# COM_GSM.net
KiCad netlist of a schematic drawn in Altium Designer
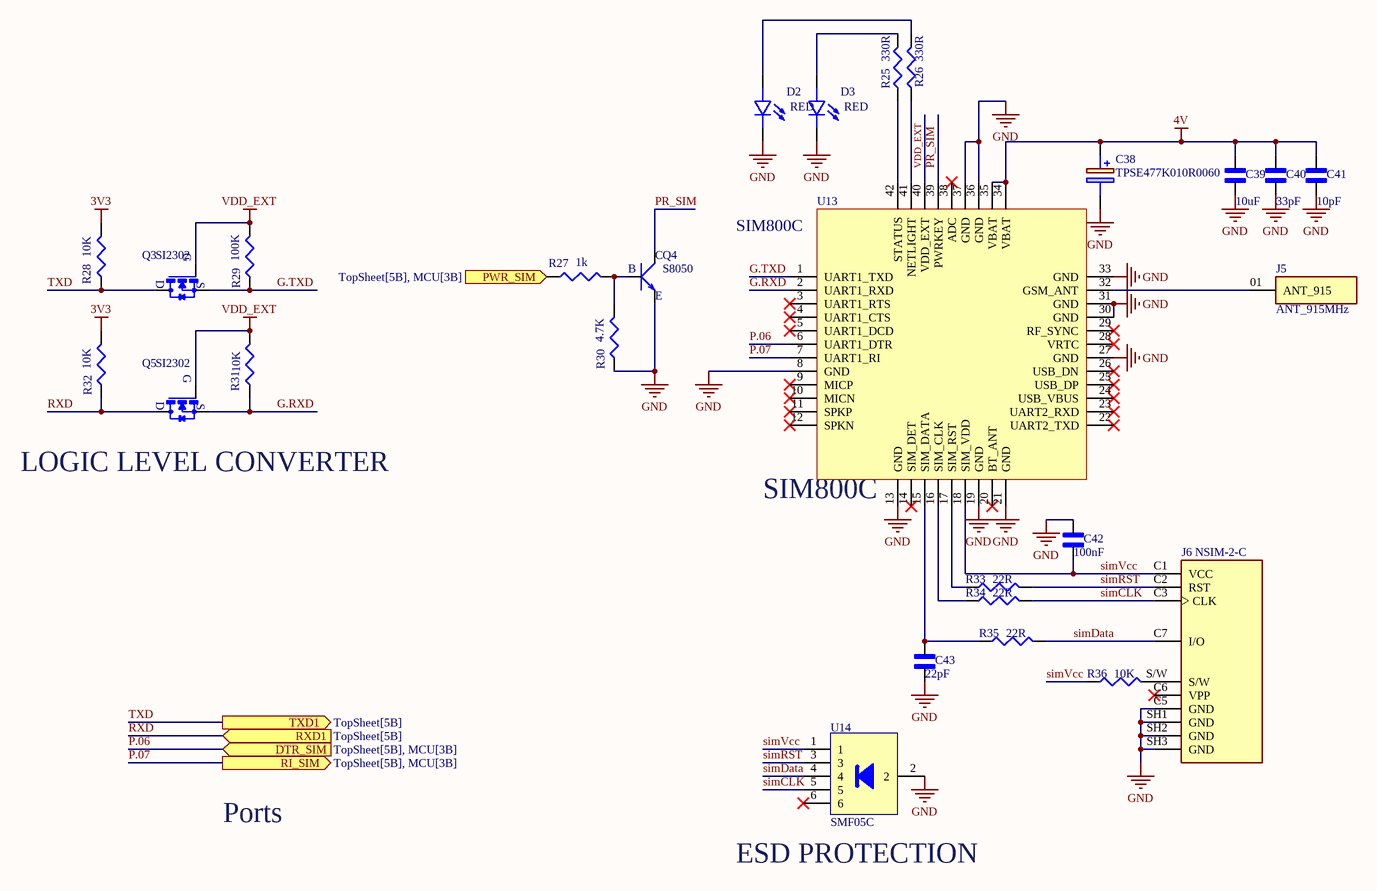
[diagram p0: COM_GSM.SchDoc]

(export (version "E")
  (design (tool "Eeschema 10.0.6"))
  (components
    (comp (ref "C38")
      (value "TPSE477K010R0060")
      (footprint "CAPPM7344X430N")
      (fields (field (name "MOUSER PART NUMBER") "581-TPSE477K010R0060"))
      (libsource (lib "TPSE477K010R0060") (part "TPSE477K010R0060"))
    )
    (comp (ref "C39")
      (value "10uF")
      (footprint "C0603")
      (fields (field (name "MF") "Murata") (field (name "MP") "GJM1555C1HR10BB01J"))
      (libsource (lib "common component") (part "Capacitor non polar"))
    )
    (comp (ref "C40")
      (value "33pF")
      (footprint "C0603")
      (fields (field (name "MF") "Murata") (field (name "MP") "GJM1555C1HR10BB01J"))
      (libsource (lib "common component") (part "Capacitor non polar"))
    )
    (comp (ref "C41")
      (value "10pF")
      (footprint "C0603")
      (fields (field (name "MF") "Murata") (field (name "MP") "GJM1555C1HR10BB01J"))
      (libsource (lib "common component") (part "Capacitor non polar"))
    )
    (comp (ref "C42")
      (value "100nF")
      (footprint "C0402")
      (fields (field (name "MF") "Murata") (field (name "MP") "GJM1555C1HR10BB01J"))
      (libsource (lib "common component") (part "Capacitor non polar"))
    )
    (comp (ref "C43")
      (value "22pF")
      (footprint "C0402")
      (fields (field (name "MF") "Murata") (field (name "MP") "GJM1555C1HR10BB01J"))
      (libsource (lib "common component") (part "Capacitor non polar"))
    )
    (comp (ref "D2")
      (value "RED")
      (footprint "0603D-B")
      (description "Generic LED SMD")
      (fields (field (name "MF") "Osram") (field (name "MP") "LHN974 RED LED 1206"))
      (libsource (lib "common component") (part "LED"))
    )
    (comp (ref "D3")
      (value "RED")
      (footprint "0603D-B")
      (description "Generic LED SMD")
      (fields (field (name "MF") "Osram") (field (name "MP") "LHN974 RED LED 1206"))
      (libsource (lib "common component") (part "LED"))
    )
    (comp (ref "J5")
      (value "ANT_915MHz")
      (footprint "SAMTEC_HTSW-101-24-LM-S")
      (fields (field (name "MP") "HTSW-101-24-LM-S"))
      (libsource (lib "ANT 915MHz") (part "ANT_915MHz"))
    )
    (comp (ref "J6")
      (value "NSIM-2-C")
      (footprint "CUI_NSIM-2-C")
      (fields (field (name "MF") "Same Sky"))
      (libsource (lib "NSIM-2-C") (part "NSIM-2-C"))
    )
    (comp (ref "Q3")
      (value "SI2302")
      (footprint "SOT23")
      (description "N-Channel 20 V 2.6A (Ta) 710mW (Ta) Surface Mount SOT-23-3 (TO-236)")
      (fields (field (name "MF") "Vishay Siliconix"))
      (libsource (lib "SI2302") (part "SI2302"))
    )
    (comp (ref "Q4")
      (value "S8050")
      (footprint "SOT95P237X112-3N")
      (description "Bipolar (BJT) Transistor NPN 25 V 500 mA 150MHz 300 mW Surface Mount SOT-23")
      (fields (field (name "MF") "UMW"))
      (libsource (lib "S8050") (part "S8050"))
    )
    (comp (ref "Q5")
      (value "SI2302")
      (footprint "SOT23")
      (description "N-Channel 20 V 2.6A (Ta) 710mW (Ta) Surface Mount SOT-23-3 (TO-236)")
      (fields (field (name "MF") "Vishay Siliconix"))
      (libsource (lib "SI2302") (part "SI2302"))
    )
    (comp (ref "R25")
      (value "330R")
      (footprint "R0603")
      (libsource (lib "common component") (part "Resistor"))
    )
    (comp (ref "R26")
      (value "330R")
      (footprint "R0603")
      (libsource (lib "common component") (part "Resistor"))
    )
    (comp (ref "R27") (value "1k") (footprint "R0603") (libsource (lib "common component") (part "Resistor")))
    (comp (ref "R28")
      (value "10K")
      (footprint "R0603")
      (libsource (lib "common component") (part "Resistor"))
    )
    (comp (ref "R29")
      (value "100K")
      (footprint "R0603")
      (libsource (lib "common component") (part "Resistor"))
    )
    (comp (ref "R30")
      (value "4.7K")
      (footprint "R0603")
      (libsource (lib "common component") (part "Resistor"))
    )
    (comp (ref "R31")
      (value "10K")
      (footprint "R0603")
      (libsource (lib "common component") (part "Resistor"))
    )
    (comp (ref "R32")
      (value "10K")
      (footprint "R0603")
      (libsource (lib "common component") (part "Resistor"))
    )
    (comp (ref "R33")
      (value "22R")
      (footprint "R0402")
      (libsource (lib "common component") (part "Resistor"))
    )
    (comp (ref "R34")
      (value "22R")
      (footprint "R0402")
      (libsource (lib "common component") (part "Resistor"))
    )
    (comp (ref "R35")
      (value "22R")
      (footprint "R0402")
      (libsource (lib "common component") (part "Resistor"))
    )
    (comp (ref "R36")
      (value "10K")
      (footprint "R0402")
      (libsource (lib "common component") (part "Resistor"))
    )
    (comp (ref "U13")
      (value "SIM800C GSM/GPRS Module")
      (footprint "SMD")
      (fields (field (name "DEVICENAME") "SIM800C"))
      (libsource (lib "SIM800C") (part "GSM_SIM800C"))
    )
    (comp (ref "U14") (value "SOT363") (footprint "SOT363") (libsource (lib "SMF05C") (part "SMF05C")))
  )
  (nets
    (net (code "1") (name "/G.RXD") (class "Default")
      (node (ref "Q5") (pin "2") (pinfunction "S_2") (pintype "passive"))
      (node (ref "R31") (pin "1") (pinfunction "1_1") (pintype "passive"))
      (node (ref "U13") (pin "2") (pinfunction "UART1_RXD_2") (pintype "passive"))
    )
    (net (code "2") (name "/G.TXD") (class "Default")
      (node (ref "Q3") (pin "2") (pinfunction "S_2") (pintype "passive"))
      (node (ref "R29") (pin "1") (pinfunction "1_1") (pintype "passive"))
      (node (ref "U13") (pin "1") (pinfunction "UART1_TXD_1") (pintype "passive"))
    )
    (net (code "3") (name "/P.06") (class "Default")
      (node (ref "U13") (pin "6") (pinfunction "UART1_DTR_6") (pintype "passive"))
    )
    (net (code "4") (name "/P.07") (class "Default")
      (node (ref "U13") (pin "7") (pinfunction "UART1_RI_7") (pintype "passive"))
    )
    (net (code "5") (name "/PR_SIM") (class "Default")
      (node (ref "Q4") (pin "3") (pinfunction "C_3") (pintype "passive"))
      (node (ref "U13") (pin "39") (pinfunction "PWRKEY_39") (pintype "passive"))
    )
    (net (code "6") (name "/PWR_SIM") (class "Default")
      (node (ref "R27") (pin "1") (pinfunction "1_1") (pintype "passive"))
    )
    (net (code "7") (name "/RXD") (class "Default")
      (node (ref "Q5") (pin "3") (pinfunction "D_3") (pintype "passive"))
      (node (ref "R32") (pin "1") (pinfunction "1_1") (pintype "passive"))
    )
    (net (code "8") (name "/TXD") (class "Default")
      (node (ref "Q3") (pin "3") (pinfunction "D_3") (pintype "passive"))
      (node (ref "R28") (pin "1") (pinfunction "1_1") (pintype "passive"))
    )
    (net (code "9") (name "/simCLK") (class "Default")
      (node (ref "J6") (pin "C3") (pinfunction "CLK_C3") (pintype "passive"))
      (node (ref "R34") (pin "2") (pinfunction "2_2") (pintype "passive"))
      (node (ref "U14") (pin "5") (pinfunction "5_5") (pintype "passive"))
    )
    (net (code "10") (name "/simData") (class "Default")
      (node (ref "J6") (pin "C7") (pinfunction "I/O_C7") (pintype "passive"))
      (node (ref "R35") (pin "2") (pinfunction "2_2") (pintype "passive"))
      (node (ref "U14") (pin "4") (pinfunction "4_4") (pintype "passive"))
    )
    (net (code "11") (name "/simRST") (class "Default")
      (node (ref "J6") (pin "C2") (pinfunction "RST_C2") (pintype "passive"))
      (node (ref "R33") (pin "2") (pinfunction "2_2") (pintype "passive"))
      (node (ref "U14") (pin "3") (pinfunction "3_3") (pintype "passive"))
    )
    (net (code "12") (name "/simVcc") (class "Default")
      (node (ref "C42") (pin "1") (pinfunction "1_1") (pintype "passive"))
      (node (ref "J6") (pin "C1") (pinfunction "VCC_C1") (pintype "passive"))
      (node (ref "R36") (pin "1") (pinfunction "1_1") (pintype "passive"))
      (node (ref "U13") (pin "18") (pinfunction "SIM_VDD_18") (pintype "passive"))
      (node (ref "U14") (pin "1") (pinfunction "1_1") (pintype "passive"))
    )
    (net (code "13") (name "3V3") (class "Default")
      (node (ref "R28") (pin "2") (pinfunction "2_2") (pintype "passive"))
      (node (ref "R32") (pin "2") (pinfunction "2_2") (pintype "passive"))
    )
    (net (code "14") (name "4V") (class "Default")
      (node (ref "C38") (pin "1") (pinfunction "+_1") (pintype "passive"))
      (node (ref "C39") (pin "2") (pinfunction "2_2") (pintype "passive"))
      (node (ref "C40") (pin "2") (pinfunction "2_2") (pintype "passive"))
      (node (ref "C41") (pin "2") (pinfunction "2_2") (pintype "passive"))
      (node (ref "U13") (pin "34") (pinfunction "VBAT_34") (pintype "passive"))
      (node (ref "U13") (pin "35") (pinfunction "VBAT_35") (pintype "passive"))
    )
    (net (code "15") (name "GND") (class "Default")
      (node (ref "C38") (pin "2") (pinfunction "-_2") (pintype "passive"))
      (node (ref "C39") (pin "1") (pinfunction "1_1") (pintype "passive"))
      (node (ref "C40") (pin "1") (pinfunction "1_1") (pintype "passive"))
      (node (ref "C41") (pin "1") (pinfunction "1_1") (pintype "passive"))
      (node (ref "C42") (pin "2") (pinfunction "2_2") (pintype "passive"))
      (node (ref "C43") (pin "1") (pinfunction "1_1") (pintype "passive"))
      (node (ref "D2") (pin "2") (pinfunction "NEG_2") (pintype "passive"))
      (node (ref "D3") (pin "2") (pinfunction "NEG_2") (pintype "passive"))
      (node (ref "J6") (pin "C5") (pinfunction "GND_C5") (pintype "passive"))
      (node (ref "J6") (pin "SH1") (pinfunction "GND_SH1") (pintype "passive"))
      (node (ref "J6") (pin "SH2") (pinfunction "GND_SH2") (pintype "passive"))
      (node (ref "J6") (pin "SH3") (pinfunction "GND_SH3") (pintype "passive"))
      (node (ref "Q4") (pin "2") (pinfunction "E_2") (pintype "passive"))
      (node (ref "R30") (pin "1") (pinfunction "1_1") (pintype "passive"))
      (node (ref "U13") (pin "13") (pinfunction "GND_13") (pintype "passive"))
      (node (ref "U13") (pin "19") (pinfunction "GND_19") (pintype "passive"))
      (node (ref "U13") (pin "21") (pinfunction "GND_21") (pintype "passive"))
      (node (ref "U13") (pin "27") (pinfunction "GND_27") (pintype "passive"))
      (node (ref "U13") (pin "30") (pinfunction "GND_30") (pintype "passive"))
      (node (ref "U13") (pin "31") (pinfunction "GND_31") (pintype "passive"))
      (node (ref "U13") (pin "33") (pinfunction "GND_33") (pintype "passive"))
      (node (ref "U13") (pin "36") (pinfunction "GND_36") (pintype "passive"))
      (node (ref "U13") (pin "37") (pinfunction "GND_37") (pintype "passive"))
      (node (ref "U13") (pin "8") (pinfunction "GND_8") (pintype "passive"))
      (node (ref "U14") (pin "2") (pinfunction "2_2") (pintype "passive"))
    )
    (net (code "16") (name "Net-(D2-POS)") (class "Default")
      (node (ref "D2") (pin "1") (pinfunction "POS_1") (pintype "passive"))
      (node (ref "R26") (pin "2") (pinfunction "2_2") (pintype "passive"))
    )
    (net (code "17") (name "Net-(D3-POS)") (class "Default")
      (node (ref "D3") (pin "1") (pinfunction "POS_1") (pintype "passive"))
      (node (ref "R25") (pin "2") (pinfunction "2_2") (pintype "passive"))
    )
    (net (code "18") (name "Net-(J5-ANT_915)") (class "Default")
      (node (ref "J5") (pin "01") (pinfunction "ANT_915_01") (pintype "passive"))
      (node (ref "U13") (pin "32") (pinfunction "GSM_ANT_32") (pintype "passive"))
    )
    (net (code "19") (name "Net-(J6-PadS{slash}W)") (class "Default")
      (node (ref "J6") (pin "S/W") (pinfunction "S/W_S/W") (pintype "passive"))
      (node (ref "R36") (pin "2") (pinfunction "2_2") (pintype "passive"))
    )
    (net (code "20") (name "Net-(Q4-B)") (class "Default")
      (node (ref "Q4") (pin "1") (pinfunction "B_1") (pintype "passive"))
      (node (ref "R27") (pin "2") (pinfunction "2_2") (pintype "passive"))
      (node (ref "R30") (pin "2") (pinfunction "2_2") (pintype "passive"))
    )
    (net (code "21") (name "Net-(U13-NETLIGHT)") (class "Default")
      (node (ref "R26") (pin "1") (pinfunction "1_1") (pintype "passive"))
      (node (ref "U13") (pin "41") (pinfunction "NETLIGHT_41") (pintype "passive"))
    )
    (net (code "22") (name "Net-(U13-SIM_CLK)") (class "Default")
      (node (ref "R34") (pin "1") (pinfunction "1_1") (pintype "passive"))
      (node (ref "U13") (pin "16") (pinfunction "SIM_CLK_16") (pintype "passive"))
    )
    (net (code "23") (name "Net-(U13-SIM_DATA)") (class "Default")
      (node (ref "C43") (pin "2") (pinfunction "2_2") (pintype "passive"))
      (node (ref "R35") (pin "1") (pinfunction "1_1") (pintype "passive"))
      (node (ref "U13") (pin "15") (pinfunction "SIM_DATA_15") (pintype "passive"))
    )
    (net (code "24") (name "Net-(U13-SIM_RST)") (class "Default")
      (node (ref "R33") (pin "1") (pinfunction "1_1") (pintype "passive"))
      (node (ref "U13") (pin "17") (pinfunction "SIM_RST_17") (pintype "passive"))
    )
    (net (code "25") (name "Net-(U13-STATUS)") (class "Default")
      (node (ref "R25") (pin "1") (pinfunction "1_1") (pintype "passive"))
      (node (ref "U13") (pin "42") (pinfunction "STATUS_42") (pintype "passive"))
    )
    (net (code "26") (name "VDD_EXT") (class "Default")
      (node (ref "Q3") (pin "1") (pinfunction "G_1") (pintype "passive"))
      (node (ref "Q5") (pin "1") (pinfunction "G_1") (pintype "passive"))
      (node (ref "R29") (pin "2") (pinfunction "2_2") (pintype "passive"))
      (node (ref "R31") (pin "2") (pinfunction "2_2") (pintype "passive"))
      (node (ref "U13") (pin "40") (pinfunction "VDD_EXT_40") (pintype "passive"))
    )
    (net (code "27") (name "unconnected-(J6-VPP-PadC6)") (class "Default")
      (node (ref "J6") (pin "C6") (pinfunction "VPP_C6") (pintype "passive+no_connect"))
    )
    (net (code "28") (name "unconnected-(U13-ADC-Pad38)") (class "Default")
      (node (ref "U13") (pin "38") (pinfunction "ADC_38") (pintype "passive+no_connect"))
    )
    (net (code "29") (name "unconnected-(U13-BT_ANT-Pad20)") (class "Default")
      (node (ref "U13") (pin "20") (pinfunction "BT_ANT_20") (pintype "passive+no_connect"))
    )
    (net (code "30") (name "unconnected-(U13-MICN-Pad10)") (class "Default")
      (node (ref "U13") (pin "10") (pinfunction "MICN_10") (pintype "passive+no_connect"))
    )
    (net (code "31") (name "unconnected-(U13-MICP-Pad9)") (class "Default")
      (node (ref "U13") (pin "9") (pinfunction "MICP_9") (pintype "passive+no_connect"))
    )
    (net (code "32") (name "unconnected-(U13-RF_SYNC-Pad29)") (class "Default")
      (node (ref "U13") (pin "29") (pinfunction "RF_SYNC_29") (pintype "passive+no_connect"))
    )
    (net (code "33") (name "unconnected-(U13-SIM_DET-Pad14)") (class "Default")
      (node (ref "U13") (pin "14") (pinfunction "SIM_DET_14") (pintype "passive+no_connect"))
    )
    (net (code "34") (name "unconnected-(U13-SPKN-Pad12)") (class "Default")
      (node (ref "U13") (pin "12") (pinfunction "SPKN_12") (pintype "passive+no_connect"))
    )
    (net (code "35") (name "unconnected-(U13-SPKP-Pad11)") (class "Default")
      (node (ref "U13") (pin "11") (pinfunction "SPKP_11") (pintype "passive+no_connect"))
    )
    (net (code "36") (name "unconnected-(U13-UART1_CTS-Pad4)") (class "Default")
      (node (ref "U13") (pin "4") (pinfunction "UART1_CTS_4") (pintype "passive+no_connect"))
    )
    (net (code "37") (name "unconnected-(U13-UART1_DCD-Pad5)") (class "Default")
      (node (ref "U13") (pin "5") (pinfunction "UART1_DCD_5") (pintype "passive+no_connect"))
    )
    (net (code "38") (name "unconnected-(U13-UART1_RTS-Pad3)") (class "Default")
      (node (ref "U13") (pin "3") (pinfunction "UART1_RTS_3") (pintype "passive+no_connect"))
    )
    (net (code "39") (name "unconnected-(U13-UART2_RXD-Pad23)") (class "Default")
      (node (ref "U13") (pin "23") (pinfunction "UART2_RXD_23") (pintype "passive+no_connect"))
    )
    (net (code "40") (name "unconnected-(U13-UART2_TXD-Pad22)") (class "Default")
      (node (ref "U13") (pin "22") (pinfunction "UART2_TXD_22") (pintype "passive+no_connect"))
    )
    (net (code "41") (name "unconnected-(U13-USB_DN-Pad26)") (class "Default")
      (node (ref "U13") (pin "26") (pinfunction "USB_DN_26") (pintype "passive+no_connect"))
    )
    (net (code "42") (name "unconnected-(U13-USB_DP-Pad25)") (class "Default")
      (node (ref "U13") (pin "25") (pinfunction "USB_DP_25") (pintype "passive+no_connect"))
    )
    (net (code "43") (name "unconnected-(U13-USB_VBUS-Pad24)") (class "Default")
      (node (ref "U13") (pin "24") (pinfunction "USB_VBUS_24") (pintype "passive+no_connect"))
    )
    (net (code "44") (name "unconnected-(U13-VRTC-Pad28)") (class "Default")
      (node (ref "U13") (pin "28") (pinfunction "VRTC_28") (pintype "passive+no_connect"))
    )
    (net (code "45") (name "unconnected-(U14-Pad6)") (class "Default")
      (node (ref "U14") (pin "6") (pinfunction "6_6") (pintype "passive+no_connect"))
    )
  )
)
